# Killswitch.net
KiCad netlist of a schematic drawn in Altium Designer
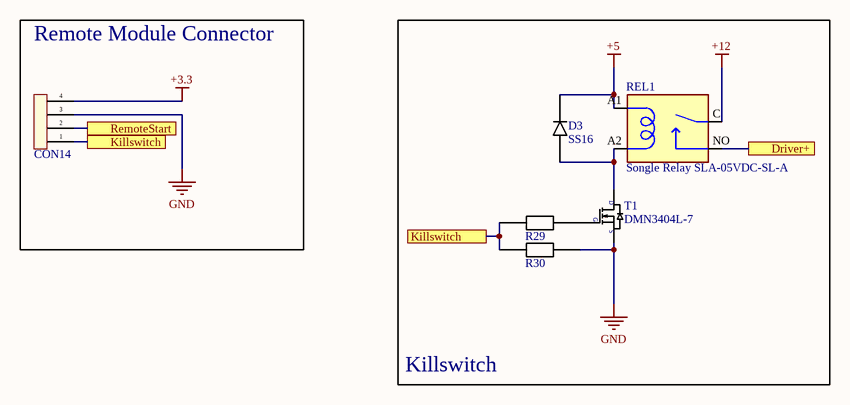
[diagram p0: Killswitch.SchDoc]

(export (version "E")
  (design (tool "Eeschema 10.0.6"))
  (components
    (comp (ref "CON14")
      (value "1x4 2.54mm THT")
      (footprint "CON_1x4_2.54MM_THT")
      (description "CON_1x4_2.54mm_THT")
      (libsource (lib "Connectors") (part "CON_1x4_2.54mm_THT"))
    )
    (comp (ref "D3")
      (value "SS16")
      (footprint "DO-214AC")
      (description "Independent 60V 700mV@1A 1A SMA(DO-214AC) Single Diodes RoHS")
      (libsource (lib "Diodes") (part "SS16"))
    )
    (comp (ref "R29")
      (value "470")
      (footprint "RES_0805")
      (description "RES_0805")
      (libsource (lib "Passives") (part "RES_0805"))
    )
    (comp (ref "R30")
      (value "4k7")
      (footprint "RES_0805")
      (description "RES_0805")
      (libsource (lib "Passives") (part "RES_0805"))
    )
    (comp (ref "REL1")
      (value "Songle Relay SLA-05VDC-SL-A")
      (footprint "TE_1-1393210-3")
      (libsource (lib "Transistors_Relays") (part "SLA-05VDC-SL-A"))
    )
    (comp (ref "T1")
      (value "DMN3404L-7")
      (footprint "SOT23-3")
      (description "N-Channel 30V 5.8A 1.4W Surface Mount SOT-23")
      (libsource (lib "Transistors_Relays") (part "DMN3404L-7"))
    )
  )
  (nets
    (net (code "1") (name "+3.3") (class "Default")
      (node (ref "CON14") (pin "4") (pinfunction "4_4") (pintype "passive"))
    )
    (net (code "2") (name "+5") (class "Default")
      (node (ref "D3") (pin "1") (pinfunction "1_1") (pintype "passive"))
      (node (ref "REL1") (pin "A1") (pinfunction "A1_A1") (pintype "passive"))
    )
    (net (code "3") (name "+12") (class "Default")
      (node (ref "REL1") (pin "C") (pinfunction "C_C") (pintype "passive"))
    )
    (net (code "4") (name "/Driver+") (class "Default")
      (node (ref "REL1") (pin "NO") (pinfunction "NO_NO") (pintype "passive"))
    )
    (net (code "5") (name "/Killswitch") (class "Default")
      (node (ref "CON14") (pin "1") (pinfunction "1_1") (pintype "passive"))
      (node (ref "R29") (pin "1") (pinfunction "1_1") (pintype "passive"))
      (node (ref "R30") (pin "1") (pinfunction "1_1") (pintype "passive"))
    )
    (net (code "6") (name "/RemoteStart") (class "Default")
      (node (ref "CON14") (pin "2") (pinfunction "2_2") (pintype "passive"))
    )
    (net (code "7") (name "GND") (class "Default")
      (node (ref "CON14") (pin "3") (pinfunction "3_3") (pintype "passive"))
      (node (ref "R30") (pin "2") (pinfunction "2_2") (pintype "passive"))
      (node (ref "T1") (pin "2") (pinfunction "2_2") (pintype "passive"))
    )
    (net (code "8") (name "Net-(D3-Pad2)") (class "Default")
      (node (ref "D3") (pin "2") (pinfunction "2_2") (pintype "passive"))
      (node (ref "REL1") (pin "A2") (pinfunction "A2_A2") (pintype "passive"))
      (node (ref "T1") (pin "3") (pinfunction "3_3") (pintype "passive"))
    )
    (net (code "9") (name "Net-(R29-Pad2)") (class "Default")
      (node (ref "R29") (pin "2") (pinfunction "2_2") (pintype "passive"))
      (node (ref "T1") (pin "1") (pinfunction "1_1") (pintype "passive"))
    )
  )
)
